# Sheet1.net
KiCad netlist of a schematic drawn in Altium Designer
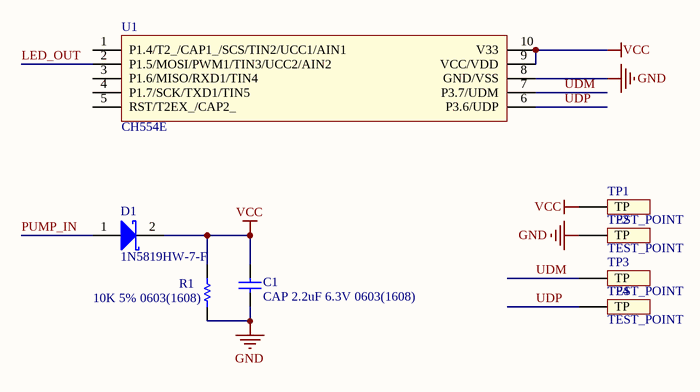
[diagram p0: Sheet1.SchDoc]

(export (version "E")
  (design (tool "Eeschema 10.0.6"))
  (components
    (comp (ref "C1")
      (value "CAP 2.2uF 6.3V 0603(1608)")
      (footprint "CAPC0603(1608)100_L")
      (description "CAP 2.2uF 6.3V ±10% 0603 (1608 Metric) Thickness 1mm SMD")
      (fields (field (name "TOLERANCE") "Â±10%"))
      (libsource (lib "Altium Content Vault") (part "CAP"))
    )
    (comp (ref "D1")
      (value "1N5819HW-7-F")
      (footprint "DIOD-SOD-123-2_V")
      (fields (field (name "MANUFACTURER") "Diodes Inc"))
      (libsource (lib "Altium Content Vault") (part "DIOD-DSKY-A1K2-2"))
    )
    (comp (ref "R1")
      (value "10K 5% 0603(1608)")
      (footprint "RESC0603(1608)_N")
      (description "10K 0.1W 5% 0603 (1608 Metric)  SMD")
      (fields (field (name "TOLERANCE") "5 %") (field (name "POWER") "0.1 W"))
      (libsource (lib "Altium Content Vault") (part "RES"))
    )
    (comp (ref "TP1")
      (value "TEST_POINT")
      (footprint "TP-SMD-1mm")
      (description "Test point")
      (libsource (lib "Blinkinlabs") (part "TEST_POINT"))
    )
    (comp (ref "TP2")
      (value "TEST_POINT")
      (footprint "TP-SMD-1mm")
      (description "Test point")
      (libsource (lib "Blinkinlabs") (part "TEST_POINT"))
    )
    (comp (ref "TP3")
      (value "TEST_POINT")
      (footprint "TP-SMD-1mm")
      (description "Test point")
      (libsource (lib "Blinkinlabs") (part "TEST_POINT"))
    )
    (comp (ref "TP4")
      (value "TEST_POINT")
      (footprint "TP-SMD-1mm")
      (description "Test point")
      (libsource (lib "Blinkinlabs") (part "TEST_POINT"))
    )
    (comp (ref "U1")
      (value "CH554E")
      (footprint "LC-MSOP-10")
      (description "8-bit enhanced USB microcontroller")
      (fields (field (name "MANUFACTURER") "WCH"))
      (libsource (lib "Blinkinlabs") (part "CH554E"))
    )
  )
  (nets
    (net (code "1") (name "/LED_OUT") (class "Default")
      (node (ref "U1") (pin "2") (pinfunction "P1.5/MOSI/PWM1/TIN3/UCC2/AIN2_2") (pintype "passive"))
    )
    (net (code "2") (name "/PUMP_IN") (class "Default")
      (node (ref "D1") (pin "1") (pinfunction "A_1") (pintype "passive"))
    )
    (net (code "3") (name "/UDM") (class "Default")
      (node (ref "TP3") (pin "1") (pinfunction "TP_1") (pintype "passive"))
      (node (ref "U1") (pin "7") (pinfunction "P3.7/UDM_7") (pintype "passive"))
    )
    (net (code "4") (name "/UDP") (class "Default")
      (node (ref "TP4") (pin "1") (pinfunction "TP_1") (pintype "passive"))
      (node (ref "U1") (pin "6") (pinfunction "P3.6/UDP_6") (pintype "passive"))
    )
    (net (code "5") (name "GND") (class "Default")
      (node (ref "C1") (pin "1") (pinfunction "1_1") (pintype "passive"))
      (node (ref "R1") (pin "1") (pinfunction "1_1") (pintype "passive"))
      (node (ref "TP2") (pin "1") (pinfunction "TP_1") (pintype "passive"))
      (node (ref "U1") (pin "8") (pinfunction "GND/VSS_8") (pintype "power_in"))
    )
    (net (code "6") (name "VCC") (class "Default")
      (node (ref "C1") (pin "2") (pinfunction "2_2") (pintype "passive"))
      (node (ref "D1") (pin "2") (pinfunction "K_2") (pintype "passive"))
      (node (ref "R1") (pin "2") (pinfunction "2_2") (pintype "passive"))
      (node (ref "TP1") (pin "1") (pinfunction "TP_1") (pintype "passive"))
      (node (ref "U1") (pin "10") (pinfunction "V33_10") (pintype "power_in"))
      (node (ref "U1") (pin "9") (pinfunction "VCC/VDD_9") (pintype "power_in"))
    )
    (net (code "7") (name "unconnected-(U1-P1.4{slash}T2_{slash}CAP1_{slash}SCS{slash}TIN2{slash}UCC1{slash}AIN1-Pad1)") (class "Default")
      (node (ref "U1") (pin "1") (pinfunction "P1.4/T2_/CAP1_/SCS/TIN2/UCC1/AIN1_1") (pintype "passive"))
    )
    (net (code "8") (name "unconnected-(U1-P1.6{slash}MISO{slash}RXD1{slash}TIN4-Pad3)") (class "Default")
      (node (ref "U1") (pin "3") (pinfunction "P1.6/MISO/RXD1/TIN4_3") (pintype "passive"))
    )
    (net (code "9") (name "unconnected-(U1-P1.7{slash}SCK{slash}TXD1{slash}TIN5-Pad4)") (class "Default")
      (node (ref "U1") (pin "4") (pinfunction "P1.7/SCK/TXD1/TIN5_4") (pintype "passive"))
    )
    (net (code "10") (name "unconnected-(U1-RST{slash}T2EX_{slash}CAP2_-Pad5)") (class "Default")
      (node (ref "U1") (pin "5") (pinfunction "RST/T2EX_/CAP2__5") (pintype "passive"))
    )
  )
)
